# 02_MCU.net
KiCad netlist of a schematic drawn in Altium Designer
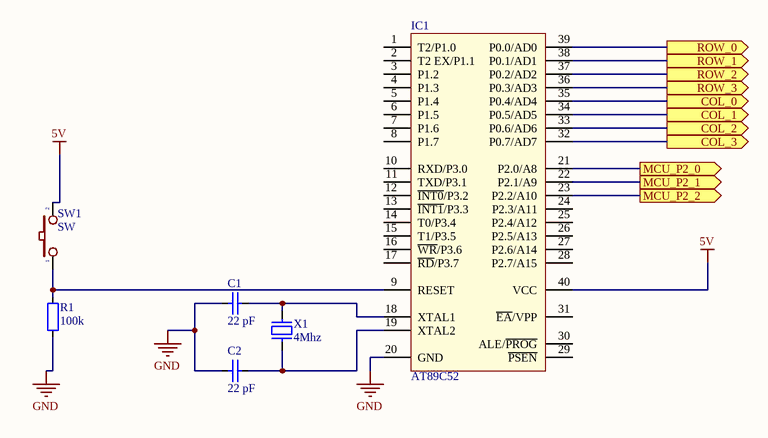
[diagram p0: [02] MCU.SchDoc]

(export (version "E")
  (design (tool "Eeschema 10.0.6"))
  (components
    (comp (ref "C1")
      (value "22 pF")
      (footprint "CAP_0402")
      (description "Capacitor")
      (fields (field (name "PUBLISHER") "Altium Limited"))
      (libsource (lib "My Library") (part "CapSMD"))
    )
    (comp (ref "C2")
      (value "22 pF")
      (footprint "CAP_0402")
      (description "Capacitor")
      (fields (field (name "PUBLISHER") "Altium Limited"))
      (libsource (lib "My Library") (part "CapSMD"))
    )
    (comp (ref "IC1")
      (value "AT89C52")
      (footprint "DIP40/W0.6")
      (description "Atmel AT89C52, 8k Byte Flash Memory , 40 Pin")
      (libsource (lib "My Library") (part "AT89C52"))
    )
    (comp (ref "R1")
      (value "100k")
      (footprint "RES-SMD-0805")
      (description "Resistor")
      (fields
        (field (name "MANUFACTURER") "Generic Components")
        (field (name "PUBLISHER") "Altium Hobart Technology Centre")
      )
      (libsource (lib "My Library") (part "Resistor - SMD"))
    )
    (comp (ref "SW1")
      (value "SW")
      (footprint "SW2")
      (description "Switch button 2 pin")
      (libsource (lib "My Library") (part "SW2"))
    )
    (comp (ref "X1")
      (value "4Mhz")
      (footprint "XT2")
      (description "Crystal For all Crystal 2pin.")
      (libsource (lib "My Library") (part "XT2"))
    )
  )
  (nets
    (net (code "1") (name "/COL_0") (class "Default")
      (node (ref "IC1") (pin "35") (pinfunction "P0.4/AD4_35") (pintype "passive"))
    )
    (net (code "2") (name "/COL_1") (class "Default")
      (node (ref "IC1") (pin "34") (pinfunction "P0.5/AD5_34") (pintype "passive"))
    )
    (net (code "3") (name "/COL_2") (class "Default")
      (node (ref "IC1") (pin "33") (pinfunction "P0.6/AD6_33") (pintype "passive"))
    )
    (net (code "4") (name "/COL_3") (class "Default")
      (node (ref "IC1") (pin "32") (pinfunction "P0.7/AD7_32") (pintype "passive"))
    )
    (net (code "5") (name "/MCU_P2_0") (class "Default")
      (node (ref "IC1") (pin "21") (pinfunction "P2.0/A8_21") (pintype "passive"))
    )
    (net (code "6") (name "/MCU_P2_1") (class "Default")
      (node (ref "IC1") (pin "22") (pinfunction "P2.1/A9_22") (pintype "passive"))
    )
    (net (code "7") (name "/MCU_P2_2") (class "Default")
      (node (ref "IC1") (pin "23") (pinfunction "P2.2/A10_23") (pintype "passive"))
    )
    (net (code "8") (name "/ROW_0") (class "Default")
      (node (ref "IC1") (pin "39") (pinfunction "P0.0/AD0_39") (pintype "passive"))
    )
    (net (code "9") (name "/ROW_1") (class "Default")
      (node (ref "IC1") (pin "38") (pinfunction "P0.1/AD1_38") (pintype "passive"))
    )
    (net (code "10") (name "/ROW_2") (class "Default")
      (node (ref "IC1") (pin "37") (pinfunction "P0.2/AD2_37") (pintype "passive"))
    )
    (net (code "11") (name "/ROW_3") (class "Default")
      (node (ref "IC1") (pin "36") (pinfunction "P0.3/AD3_36") (pintype "passive"))
    )
    (net (code "12") (name "5V") (class "Default")
      (node (ref "IC1") (pin "40") (pinfunction "VCC_40") (pintype "power_in"))
      (node (ref "SW1") (pin "2") (pinfunction "2_2") (pintype "passive"))
    )
    (net (code "13") (name "GND") (class "Default")
      (node (ref "C1") (pin "1") (pinfunction "1_1") (pintype "passive"))
      (node (ref "C2") (pin "2") (pinfunction "2_2") (pintype "passive"))
      (node (ref "IC1") (pin "20") (pinfunction "GND_20") (pintype "open_emitter"))
      (node (ref "R1") (pin "1") (pinfunction "1_1") (pintype "passive"))
    )
    (net (code "14") (name "Net-(IC1-RESET)") (class "Default")
      (node (ref "IC1") (pin "9") (pinfunction "RESET_9") (pintype "passive"))
      (node (ref "R1") (pin "2") (pinfunction "2_2") (pintype "passive"))
      (node (ref "SW1") (pin "1") (pinfunction "1_1") (pintype "passive"))
    )
    (net (code "15") (name "Net-(IC1-XTAL1)") (class "Default")
      (node (ref "C1") (pin "2") (pinfunction "2_2") (pintype "passive"))
      (node (ref "IC1") (pin "18") (pinfunction "XTAL1_18") (pintype "passive"))
      (node (ref "X1") (pin "1") (pinfunction "1_1") (pintype "passive"))
    )
    (net (code "16") (name "Net-(IC1-XTAL2)") (class "Default")
      (node (ref "C2") (pin "1") (pinfunction "1_1") (pintype "passive"))
      (node (ref "IC1") (pin "19") (pinfunction "XTAL2_19") (pintype "passive"))
      (node (ref "X1") (pin "2") (pinfunction "2_2") (pintype "passive"))
    )
    (net (code "17") (name "unconnected-(IC1-ALE{slash}~{PROG}-Pad30)") (class "Default")
      (node (ref "IC1") (pin "30") (pinfunction "ALE/~{PROG}_30") (pintype "passive"))
    )
    (net (code "18") (name "unconnected-(IC1-P1.2-Pad3)") (class "Default")
      (node (ref "IC1") (pin "3") (pinfunction "P1.2_3") (pintype "passive"))
    )
    (net (code "19") (name "unconnected-(IC1-P1.3-Pad4)") (class "Default")
      (node (ref "IC1") (pin "4") (pinfunction "P1.3_4") (pintype "passive"))
    )
    (net (code "20") (name "unconnected-(IC1-P1.4-Pad5)") (class "Default")
      (node (ref "IC1") (pin "5") (pinfunction "P1.4_5") (pintype "passive"))
    )
    (net (code "21") (name "unconnected-(IC1-P1.5-Pad6)") (class "Default")
      (node (ref "IC1") (pin "6") (pinfunction "P1.5_6") (pintype "passive"))
    )
    (net (code "22") (name "unconnected-(IC1-P1.6-Pad7)") (class "Default")
      (node (ref "IC1") (pin "7") (pinfunction "P1.6_7") (pintype "passive"))
    )
    (net (code "23") (name "unconnected-(IC1-P1.7-Pad8)") (class "Default")
      (node (ref "IC1") (pin "8") (pinfunction "P1.7_8") (pintype "passive"))
    )
    (net (code "24") (name "unconnected-(IC1-P2.3{slash}A11-Pad24)") (class "Default")
      (node (ref "IC1") (pin "24") (pinfunction "P2.3/A11_24") (pintype "passive"))
    )
    (net (code "25") (name "unconnected-(IC1-P2.4{slash}A12-Pad25)") (class "Default")
      (node (ref "IC1") (pin "25") (pinfunction "P2.4/A12_25") (pintype "passive"))
    )
    (net (code "26") (name "unconnected-(IC1-P2.5{slash}A13-Pad26)") (class "Default")
      (node (ref "IC1") (pin "26") (pinfunction "P2.5/A13_26") (pintype "passive"))
    )
    (net (code "27") (name "unconnected-(IC1-P2.6{slash}A14-Pad27)") (class "Default")
      (node (ref "IC1") (pin "27") (pinfunction "P2.6/A14_27") (pintype "passive"))
    )
    (net (code "28") (name "unconnected-(IC1-P2.7{slash}A15-Pad28)") (class "Default")
      (node (ref "IC1") (pin "28") (pinfunction "P2.7/A15_28") (pintype "passive"))
    )
    (net (code "29") (name "unconnected-(IC1-RXD{slash}P3.0-Pad10)") (class "Default")
      (node (ref "IC1") (pin "10") (pinfunction "RXD/P3.0_10") (pintype "passive"))
    )
    (net (code "30") (name "unconnected-(IC1-T0{slash}P3.4-Pad14)") (class "Default")
      (node (ref "IC1") (pin "14") (pinfunction "T0/P3.4_14") (pintype "passive"))
    )
    (net (code "31") (name "unconnected-(IC1-T1{slash}P3.5-Pad15)") (class "Default")
      (node (ref "IC1") (pin "15") (pinfunction "T1/P3.5_15") (pintype "passive"))
    )
    (net (code "32") (name "unconnected-(IC1-T2_EX{slash}P1.1-Pad2)") (class "Default")
      (node (ref "IC1") (pin "2") (pinfunction "T2_EX/P1.1_2") (pintype "passive"))
    )
    (net (code "33") (name "unconnected-(IC1-T2{slash}P1.0-Pad1)") (class "Default")
      (node (ref "IC1") (pin "1") (pinfunction "T2/P1.0_1") (pintype "passive"))
    )
    (net (code "34") (name "unconnected-(IC1-TXD{slash}P3.1-Pad11)") (class "Default")
      (node (ref "IC1") (pin "11") (pinfunction "TXD/P3.1_11") (pintype "passive"))
    )
    (net (code "35") (name "unconnected-(IC1-~{EA}{slash}VPP-Pad31)") (class "Default")
      (node (ref "IC1") (pin "31") (pinfunction "~{EA}/VPP_31") (pintype "passive"))
    )
    (net (code "36") (name "unconnected-(IC1-~{INT0}{slash}P3.2-Pad12)") (class "Default")
      (node (ref "IC1") (pin "12") (pinfunction "~{INT0}/P3.2_12") (pintype "passive"))
    )
    (net (code "37") (name "unconnected-(IC1-~{INT1}{slash}P3.3-Pad13)") (class "Default")
      (node (ref "IC1") (pin "13") (pinfunction "~{INT1}/P3.3_13") (pintype "passive"))
    )
    (net (code "38") (name "unconnected-(IC1-~{PSEN}-Pad29)") (class "Default")
      (node (ref "IC1") (pin "29") (pinfunction "~{PSEN}_29") (pintype "passive"))
    )
    (net (code "39") (name "unconnected-(IC1-~{RD}{slash}P3.7-Pad17)") (class "Default")
      (node (ref "IC1") (pin "17") (pinfunction "~{RD}/P3.7_17") (pintype "passive"))
    )
    (net (code "40") (name "unconnected-(IC1-~{WR}{slash}P3.6-Pad16)") (class "Default")
      (node (ref "IC1") (pin "16") (pinfunction "~{WR}/P3.6_16") (pintype "passive"))
    )
  )
)
